# catch_the_light_initial.net
KiCad netlist of a schematic drawn in EAGLE
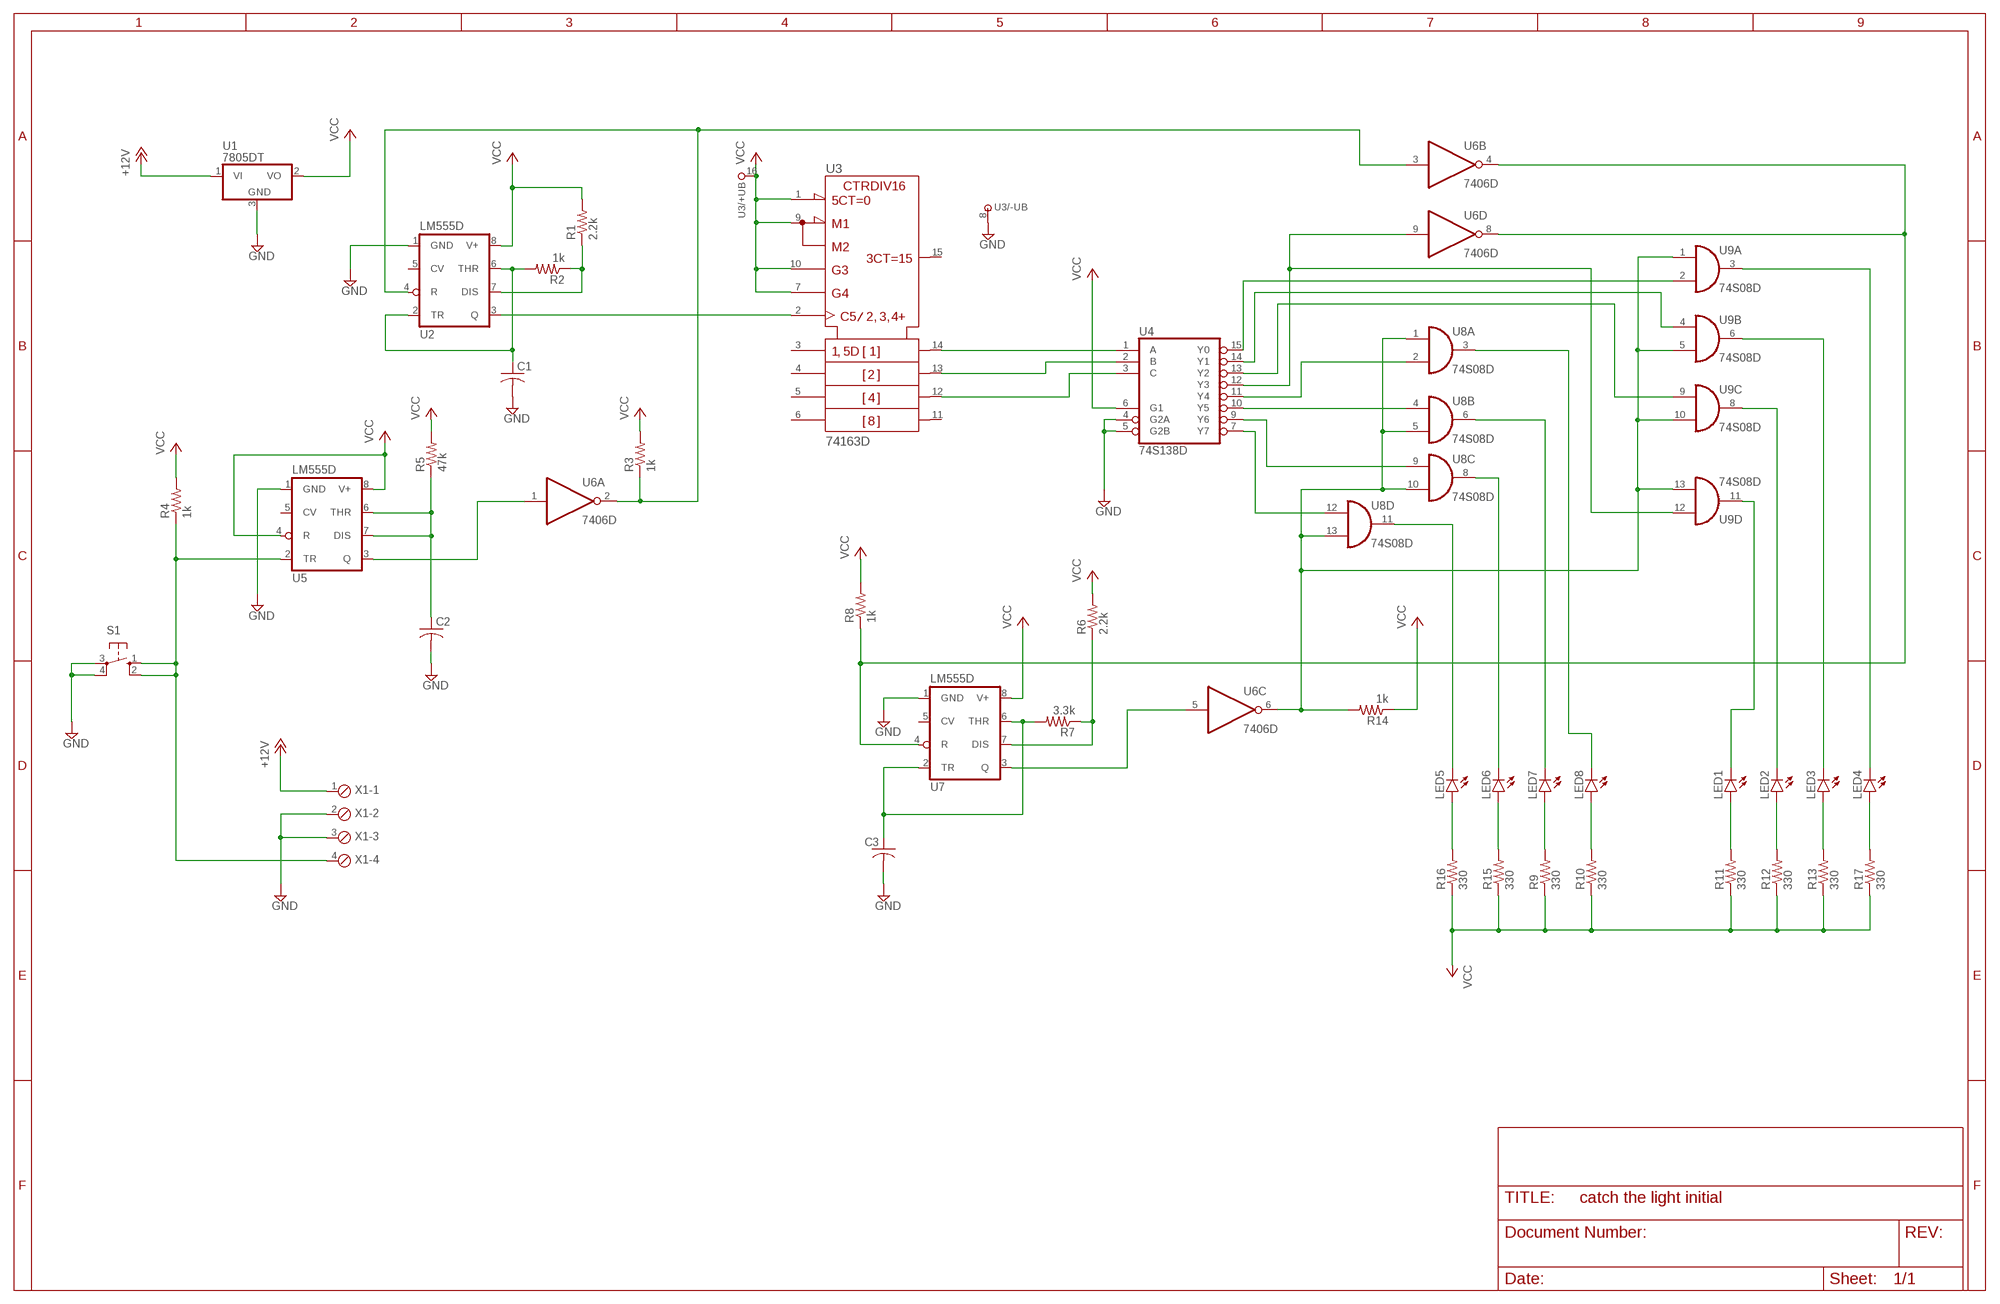
[diagram p0: schematic, sheet 1]

(export (version "E")
  (design (tool "Eeschema 10.0.6"))
  (components
    (comp (ref "C1")
      (value "C-USC0805")
      (footprint "eagle-import:C0805")
      (libsource (lib "eagle-import") (part "C-USC0805"))
    )
    (comp (ref "C2")
      (value "C-USC0805")
      (footprint "eagle-import:C0805")
      (libsource (lib "eagle-import") (part "C-USC0805"))
    )
    (comp (ref "C3")
      (value "C-USC0805")
      (footprint "eagle-import:C0805")
      (libsource (lib "eagle-import") (part "C-USC0805"))
    )
    (comp (ref "LED1")
      (value "LEDCHIP-LED0805")
      (footprint "eagle-import:CHIP-LED0805")
      (libsource (lib "eagle-import") (part "LEDCHIP-LED0805"))
    )
    (comp (ref "LED2")
      (value "LEDCHIP-LED0805")
      (footprint "eagle-import:CHIP-LED0805")
      (libsource (lib "eagle-import") (part "LEDCHIP-LED0805"))
    )
    (comp (ref "LED3")
      (value "LEDCHIP-LED0805")
      (footprint "eagle-import:CHIP-LED0805")
      (libsource (lib "eagle-import") (part "LEDCHIP-LED0805"))
    )
    (comp (ref "LED4")
      (value "LEDCHIP-LED0805")
      (footprint "eagle-import:CHIP-LED0805")
      (libsource (lib "eagle-import") (part "LEDCHIP-LED0805"))
    )
    (comp (ref "LED5")
      (value "LEDCHIP-LED0805")
      (footprint "eagle-import:CHIP-LED0805")
      (libsource (lib "eagle-import") (part "LEDCHIP-LED0805"))
    )
    (comp (ref "LED6")
      (value "LEDCHIP-LED0805")
      (footprint "eagle-import:CHIP-LED0805")
      (libsource (lib "eagle-import") (part "LEDCHIP-LED0805"))
    )
    (comp (ref "LED7")
      (value "LEDCHIP-LED0805")
      (footprint "eagle-import:CHIP-LED0805")
      (libsource (lib "eagle-import") (part "LEDCHIP-LED0805"))
    )
    (comp (ref "LED8")
      (value "LEDCHIP-LED0805")
      (footprint "eagle-import:CHIP-LED0805")
      (libsource (lib "eagle-import") (part "LEDCHIP-LED0805"))
    )
    (comp (ref "R1")
      (value "2.2k")
      (footprint "eagle-import:R0805")
      (libsource (lib "eagle-import") (part "R-US_R0805"))
    )
    (comp (ref "R2")
      (value "1k")
      (footprint "eagle-import:R0805")
      (libsource (lib "eagle-import") (part "R-US_R0805"))
    )
    (comp (ref "R3")
      (value "1k")
      (footprint "eagle-import:R0805")
      (libsource (lib "eagle-import") (part "R-US_R0805"))
    )
    (comp (ref "R4")
      (value "1k")
      (footprint "eagle-import:R0805")
      (libsource (lib "eagle-import") (part "R-US_R0805"))
    )
    (comp (ref "R5")
      (value "47k")
      (footprint "eagle-import:R0805")
      (libsource (lib "eagle-import") (part "R-US_R0805"))
    )
    (comp (ref "R6")
      (value "2.2k")
      (footprint "eagle-import:R0805")
      (libsource (lib "eagle-import") (part "R-US_R0805"))
    )
    (comp (ref "R7")
      (value "3.3k")
      (footprint "eagle-import:R0805")
      (libsource (lib "eagle-import") (part "R-US_R0805"))
    )
    (comp (ref "R8")
      (value "1k")
      (footprint "eagle-import:R0805")
      (libsource (lib "eagle-import") (part "R-US_R0805"))
    )
    (comp (ref "R9")
      (value "330")
      (footprint "eagle-import:R0805")
      (libsource (lib "eagle-import") (part "R-US_R0805"))
    )
    (comp (ref "R10")
      (value "330")
      (footprint "eagle-import:R0805")
      (libsource (lib "eagle-import") (part "R-US_R0805"))
    )
    (comp (ref "R11")
      (value "330")
      (footprint "eagle-import:R0805")
      (libsource (lib "eagle-import") (part "R-US_R0805"))
    )
    (comp (ref "R12")
      (value "330")
      (footprint "eagle-import:R0805")
      (libsource (lib "eagle-import") (part "R-US_R0805"))
    )
    (comp (ref "R13")
      (value "330")
      (footprint "eagle-import:R0805")
      (libsource (lib "eagle-import") (part "R-US_R0805"))
    )
    (comp (ref "R14")
      (value "1k")
      (footprint "eagle-import:R0805")
      (libsource (lib "eagle-import") (part "R-US_R0805"))
    )
    (comp (ref "R15")
      (value "330")
      (footprint "eagle-import:R0805")
      (libsource (lib "eagle-import") (part "R-US_R0805"))
    )
    (comp (ref "R16")
      (value "330")
      (footprint "eagle-import:R0805")
      (libsource (lib "eagle-import") (part "R-US_R0805"))
    )
    (comp (ref "R17")
      (value "330")
      (footprint "eagle-import:R0805")
      (libsource (lib "eagle-import") (part "R-US_R0805"))
    )
    (comp (ref "S1")
      (value "10-XX")
      (footprint "eagle-import:B3F-10XX")
      (fields (field (name "MPN") "B3F-1000"))
      (libsource (lib "eagle-import") (part "10-XX"))
    )
    (comp (ref "U1")
      (value "7805DT")
      (footprint "eagle-import:TO252")
      (libsource (lib "eagle-import") (part "78DT05"))
    )
    (comp (ref "U2")
      (value "LM555D")
      (footprint "eagle-import:SO08")
      (libsource (lib "eagle-import") (part "555DLM"))
    )
    (comp (ref "U3")
      (value "74163D")
      (footprint "eagle-import:SO16")
      (libsource (lib "eagle-import") (part "74163D"))
    )
    (comp (ref "U4")
      (value "74S138D")
      (footprint "eagle-import:SO16")
      (libsource (lib "eagle-import") (part "74138DS"))
    )
    (comp (ref "U5")
      (value "LM555D")
      (footprint "eagle-import:SO08")
      (libsource (lib "eagle-import") (part "555DLM"))
    )
    (comp (ref "U6")
      (value "7406D")
      (footprint "eagle-import:SO14")
      (libsource (lib "eagle-import") (part "7406D"))
    )
    (comp (ref "U7")
      (value "LM555D")
      (footprint "eagle-import:SO08")
      (libsource (lib "eagle-import") (part "555DLM"))
    )
    (comp (ref "U8")
      (value "74S08D")
      (footprint "eagle-import:SO14")
      (libsource (lib "eagle-import") (part "7408DS"))
    )
    (comp (ref "U9")
      (value "74S08D")
      (footprint "eagle-import:SO14")
      (libsource (lib "eagle-import") (part "7408DS"))
    )
    (comp (ref "X1")
      (value "MPT4")
      (footprint "eagle-import:4POL254")
      (libsource (lib "eagle-import") (part "MPT4"))
    )
  )
  (nets
    (net (code "1") (name "+12V") (class "Default")
      (node (ref "U1") (pin "1") (pinfunction "VI_1") (pintype "input"))
      (node (ref "X1") (pin "1") (pinfunction "1_1") (pintype "passive"))
    )
    (net (code "2") (name "GND") (class "Default")
      (node (ref "C1") (pin "2") (pinfunction "2_2") (pintype "passive"))
      (node (ref "C2") (pin "2") (pinfunction "2_2") (pintype "passive"))
      (node (ref "C3") (pin "2") (pinfunction "2_2") (pintype "passive"))
      (node (ref "S1") (pin "3") (pinfunction "P_3") (pintype "passive"))
      (node (ref "S1") (pin "4") (pinfunction "P1_4") (pintype "passive"))
      (node (ref "U1") (pin "3") (pinfunction "GND_3") (pintype "passive"))
      (node (ref "U2") (pin "1") (pinfunction "GND_1") (pintype "power_in"))
      (node (ref "U3") (pin "8") (pinfunction "-UB_8") (pintype "power_in"))
      (node (ref "U4") (pin "4") (pinfunction "G2A_4") (pintype "input"))
      (node (ref "U4") (pin "5") (pinfunction "G2B_5") (pintype "input"))
      (node (ref "U5") (pin "1") (pinfunction "GND_1") (pintype "power_in"))
      (node (ref "U7") (pin "1") (pinfunction "GND_1") (pintype "power_in"))
      (node (ref "X1") (pin "2") (pinfunction "1_2") (pintype "passive"))
      (node (ref "X1") (pin "3") (pinfunction "1_3") (pintype "passive"))
    )
    (net (code "3") (name "Net-(LED1-PadA)") (class "Default")
      (node (ref "LED1") (pin "A") (pinfunction "A_A") (pintype "passive"))
      (node (ref "R11") (pin "2") (pinfunction "2_2") (pintype "passive"))
    )
    (net (code "4") (name "Net-(LED2-PadA)") (class "Default")
      (node (ref "LED2") (pin "A") (pinfunction "A_A") (pintype "passive"))
      (node (ref "R12") (pin "2") (pinfunction "2_2") (pintype "passive"))
    )
    (net (code "5") (name "Net-(LED3-PadA)") (class "Default")
      (node (ref "LED3") (pin "A") (pinfunction "A_A") (pintype "passive"))
      (node (ref "R13") (pin "2") (pinfunction "2_2") (pintype "passive"))
    )
    (net (code "6") (name "Net-(LED4-PadA)") (class "Default")
      (node (ref "LED4") (pin "A") (pinfunction "A_A") (pintype "passive"))
      (node (ref "R17") (pin "2") (pinfunction "2_2") (pintype "passive"))
    )
    (net (code "7") (name "Net-(LED5-PadA)") (class "Default")
      (node (ref "LED5") (pin "A") (pinfunction "A_A") (pintype "passive"))
      (node (ref "R16") (pin "2") (pinfunction "2_2") (pintype "passive"))
    )
    (net (code "8") (name "Net-(LED6-PadA)") (class "Default")
      (node (ref "LED6") (pin "A") (pinfunction "A_A") (pintype "passive"))
      (node (ref "R15") (pin "2") (pinfunction "2_2") (pintype "passive"))
    )
    (net (code "9") (name "Net-(LED7-PadA)") (class "Default")
      (node (ref "LED7") (pin "A") (pinfunction "A_A") (pintype "passive"))
      (node (ref "R9") (pin "2") (pinfunction "2_2") (pintype "passive"))
    )
    (net (code "10") (name "Net-(LED8-PadA)") (class "Default")
      (node (ref "LED8") (pin "A") (pinfunction "A_A") (pintype "passive"))
      (node (ref "R10") (pin "2") (pinfunction "2_2") (pintype "passive"))
    )
    (net (code "11") (name "Net-(S1-S)") (class "Default")
      (node (ref "R4") (pin "1") (pinfunction "1_1") (pintype "passive"))
      (node (ref "S1") (pin "1") (pinfunction "S_1") (pintype "passive"))
      (node (ref "S1") (pin "2") (pinfunction "S1_2") (pintype "passive"))
      (node (ref "U5") (pin "2") (pinfunction "TR_2") (pintype "input"))
      (node (ref "X1") (pin "4") (pinfunction "1_4") (pintype "passive"))
    )
    (net (code "12") (name "Net-(U2-DIS)") (class "Default")
      (node (ref "R1") (pin "1") (pinfunction "1_1") (pintype "passive"))
      (node (ref "R2") (pin "1") (pinfunction "1_1") (pintype "passive"))
      (node (ref "U2") (pin "7") (pinfunction "DIS_7") (pintype "input"))
    )
    (net (code "13") (name "Net-(U2-Q)") (class "Default")
      (node (ref "U2") (pin "3") (pinfunction "Q_3") (pintype "output"))
      (node (ref "U3") (pin "2") (pinfunction "CLK_2") (pintype "input"))
    )
    (net (code "14") (name "Net-(U2-R)") (class "Default")
      (node (ref "R3") (pin "1") (pinfunction "1_1") (pintype "passive"))
      (node (ref "U2") (pin "4") (pinfunction "R_4") (pintype "input"))
      (node (ref "U6") (pin "2") (pinfunction "O_2") (pintype "open_collector"))
      (node (ref "U6") (pin "3") (pinfunction "I_3") (pintype "input"))
    )
    (net (code "15") (name "Net-(U2-THR)") (class "Default")
      (node (ref "C1") (pin "1") (pinfunction "1_1") (pintype "passive"))
      (node (ref "R2") (pin "2") (pinfunction "2_2") (pintype "passive"))
      (node (ref "U2") (pin "2") (pinfunction "TR_2") (pintype "input"))
      (node (ref "U2") (pin "6") (pinfunction "THR_6") (pintype "input"))
    )
    (net (code "16") (name "Net-(U3C-QA)") (class "Default")
      (node (ref "U3") (pin "14") (pinfunction "QA_14") (pintype "output"))
      (node (ref "U4") (pin "1") (pinfunction "A_1") (pintype "input"))
    )
    (net (code "17") (name "Net-(U3C-QB)") (class "Default")
      (node (ref "U3") (pin "13") (pinfunction "QB_13") (pintype "output"))
      (node (ref "U4") (pin "2") (pinfunction "B_2") (pintype "input"))
    )
    (net (code "18") (name "Net-(U3C-QC)") (class "Default")
      (node (ref "U3") (pin "12") (pinfunction "QC_12") (pintype "output"))
      (node (ref "U4") (pin "3") (pinfunction "C_3") (pintype "input"))
    )
    (net (code "19") (name "Net-(U4A-Y0)") (class "Default")
      (node (ref "U4") (pin "15") (pinfunction "Y0_15") (pintype "output"))
      (node (ref "U9") (pin "2") (pinfunction "I1_2") (pintype "input"))
    )
    (net (code "20") (name "Net-(U4A-Y1)") (class "Default")
      (node (ref "U4") (pin "14") (pinfunction "Y1_14") (pintype "output"))
      (node (ref "U9") (pin "4") (pinfunction "I0_4") (pintype "input"))
    )
    (net (code "21") (name "Net-(U4A-Y2)") (class "Default")
      (node (ref "U4") (pin "13") (pinfunction "Y2_13") (pintype "output"))
      (node (ref "U9") (pin "9") (pinfunction "I0_9") (pintype "input"))
    )
    (net (code "22") (name "Net-(U4A-Y3)") (class "Default")
      (node (ref "U4") (pin "12") (pinfunction "Y3_12") (pintype "output"))
      (node (ref "U6") (pin "9") (pinfunction "I_9") (pintype "input"))
      (node (ref "U9") (pin "12") (pinfunction "I0_12") (pintype "input"))
    )
    (net (code "23") (name "Net-(U4A-Y4)") (class "Default")
      (node (ref "U4") (pin "11") (pinfunction "Y4_11") (pintype "output"))
      (node (ref "U8") (pin "2") (pinfunction "I1_2") (pintype "input"))
    )
    (net (code "24") (name "Net-(U4A-Y5)") (class "Default")
      (node (ref "U4") (pin "10") (pinfunction "Y5_10") (pintype "output"))
      (node (ref "U8") (pin "4") (pinfunction "I0_4") (pintype "input"))
    )
    (net (code "25") (name "Net-(U4A-Y6)") (class "Default")
      (node (ref "U4") (pin "9") (pinfunction "Y6_9") (pintype "output"))
      (node (ref "U8") (pin "9") (pinfunction "I0_9") (pintype "input"))
    )
    (net (code "26") (name "Net-(U4A-Y7)") (class "Default")
      (node (ref "U4") (pin "7") (pinfunction "Y7_7") (pintype "output"))
      (node (ref "U8") (pin "12") (pinfunction "I0_12") (pintype "input"))
    )
    (net (code "27") (name "Net-(U5-DIS)") (class "Default")
      (node (ref "C2") (pin "1") (pinfunction "1_1") (pintype "passive"))
      (node (ref "R5") (pin "1") (pinfunction "1_1") (pintype "passive"))
      (node (ref "U5") (pin "6") (pinfunction "THR_6") (pintype "input"))
      (node (ref "U5") (pin "7") (pinfunction "DIS_7") (pintype "input"))
    )
    (net (code "28") (name "Net-(U5-Q)") (class "Default")
      (node (ref "U5") (pin "3") (pinfunction "Q_3") (pintype "output"))
      (node (ref "U6") (pin "1") (pinfunction "I_1") (pintype "input"))
    )
    (net (code "29") (name "Net-(U6B-O)") (class "Default")
      (node (ref "R8") (pin "1") (pinfunction "1_1") (pintype "passive"))
      (node (ref "U6") (pin "4") (pinfunction "O_4") (pintype "open_collector"))
      (node (ref "U6") (pin "8") (pinfunction "O_8") (pintype "open_collector"))
      (node (ref "U7") (pin "4") (pinfunction "R_4") (pintype "input"))
    )
    (net (code "30") (name "Net-(U6C-I)") (class "Default")
      (node (ref "U6") (pin "5") (pinfunction "I_5") (pintype "input"))
      (node (ref "U7") (pin "3") (pinfunction "Q_3") (pintype "output"))
    )
    (net (code "31") (name "Net-(U6C-O)") (class "Default")
      (node (ref "R14") (pin "2") (pinfunction "2_2") (pintype "passive"))
      (node (ref "U6") (pin "6") (pinfunction "O_6") (pintype "open_collector"))
      (node (ref "U8") (pin "1") (pinfunction "I0_1") (pintype "input"))
      (node (ref "U8") (pin "10") (pinfunction "I1_10") (pintype "input"))
      (node (ref "U8") (pin "13") (pinfunction "I1_13") (pintype "input"))
      (node (ref "U8") (pin "5") (pinfunction "I1_5") (pintype "input"))
      (node (ref "U9") (pin "1") (pinfunction "I0_1") (pintype "input"))
      (node (ref "U9") (pin "10") (pinfunction "I1_10") (pintype "input"))
      (node (ref "U9") (pin "13") (pinfunction "I1_13") (pintype "input"))
      (node (ref "U9") (pin "5") (pinfunction "I1_5") (pintype "input"))
    )
    (net (code "32") (name "Net-(U7-DIS)") (class "Default")
      (node (ref "R6") (pin "1") (pinfunction "1_1") (pintype "passive"))
      (node (ref "R7") (pin "1") (pinfunction "1_1") (pintype "passive"))
      (node (ref "U7") (pin "7") (pinfunction "DIS_7") (pintype "input"))
    )
    (net (code "33") (name "Net-(U7-THR)") (class "Default")
      (node (ref "C3") (pin "1") (pinfunction "1_1") (pintype "passive"))
      (node (ref "R7") (pin "2") (pinfunction "2_2") (pintype "passive"))
      (node (ref "U7") (pin "2") (pinfunction "TR_2") (pintype "input"))
      (node (ref "U7") (pin "6") (pinfunction "THR_6") (pintype "input"))
    )
    (net (code "34") (name "Net-(U8A-O)") (class "Default")
      (node (ref "LED8") (pin "C") (pinfunction "C_C") (pintype "passive"))
      (node (ref "U8") (pin "3") (pinfunction "O_3") (pintype "output"))
    )
    (net (code "35") (name "Net-(U8B-O)") (class "Default")
      (node (ref "LED7") (pin "C") (pinfunction "C_C") (pintype "passive"))
      (node (ref "U8") (pin "6") (pinfunction "O_6") (pintype "output"))
    )
    (net (code "36") (name "Net-(U8C-O)") (class "Default")
      (node (ref "LED6") (pin "C") (pinfunction "C_C") (pintype "passive"))
      (node (ref "U8") (pin "8") (pinfunction "O_8") (pintype "output"))
    )
    (net (code "37") (name "Net-(U8D-O)") (class "Default")
      (node (ref "LED5") (pin "C") (pinfunction "C_C") (pintype "passive"))
      (node (ref "U8") (pin "11") (pinfunction "O_11") (pintype "output"))
    )
    (net (code "38") (name "Net-(U9A-O)") (class "Default")
      (node (ref "LED4") (pin "C") (pinfunction "C_C") (pintype "passive"))
      (node (ref "U9") (pin "3") (pinfunction "O_3") (pintype "output"))
    )
    (net (code "39") (name "Net-(U9B-O)") (class "Default")
      (node (ref "LED3") (pin "C") (pinfunction "C_C") (pintype "passive"))
      (node (ref "U9") (pin "6") (pinfunction "O_6") (pintype "output"))
    )
    (net (code "40") (name "Net-(U9C-O)") (class "Default")
      (node (ref "LED2") (pin "C") (pinfunction "C_C") (pintype "passive"))
      (node (ref "U9") (pin "8") (pinfunction "O_8") (pintype "output"))
    )
    (net (code "41") (name "Net-(U9D-O)") (class "Default")
      (node (ref "LED1") (pin "C") (pinfunction "C_C") (pintype "passive"))
      (node (ref "U9") (pin "11") (pinfunction "O_11") (pintype "output"))
    )
    (net (code "42") (name "VCC") (class "Default")
      (node (ref "R1") (pin "2") (pinfunction "2_2") (pintype "passive"))
      (node (ref "R10") (pin "1") (pinfunction "1_1") (pintype "passive"))
      (node (ref "R11") (pin "1") (pinfunction "1_1") (pintype "passive"))
      (node (ref "R12") (pin "1") (pinfunction "1_1") (pintype "passive"))
      (node (ref "R13") (pin "1") (pinfunction "1_1") (pintype "passive"))
      (node (ref "R14") (pin "1") (pinfunction "1_1") (pintype "passive"))
      (node (ref "R15") (pin "1") (pinfunction "1_1") (pintype "passive"))
      (node (ref "R16") (pin "1") (pinfunction "1_1") (pintype "passive"))
      (node (ref "R17") (pin "1") (pinfunction "1_1") (pintype "passive"))
      (node (ref "R3") (pin "2") (pinfunction "2_2") (pintype "passive"))
      (node (ref "R4") (pin "2") (pinfunction "2_2") (pintype "passive"))
      (node (ref "R5") (pin "2") (pinfunction "2_2") (pintype "passive"))
      (node (ref "R6") (pin "2") (pinfunction "2_2") (pintype "passive"))
      (node (ref "R8") (pin "2") (pinfunction "2_2") (pintype "passive"))
      (node (ref "R9") (pin "1") (pinfunction "1_1") (pintype "passive"))
      (node (ref "U1") (pin "2") (pinfunction "VO_2") (pintype "passive"))
      (node (ref "U2") (pin "8") (pinfunction "V+_8") (pintype "power_in"))
      (node (ref "U3") (pin "1") (pinfunction "~{CLR}_1") (pintype "input"))
      (node (ref "U3") (pin "10") (pinfunction "ENT_10") (pintype "input"))
      (node (ref "U3") (pin "16") (pinfunction "+UB_16") (pintype "power_in"))
      (node (ref "U3") (pin "7") (pinfunction "ENP_7") (pintype "input"))
      (node (ref "U3") (pin "9") (pinfunction "~{LOAD}_9") (pintype "input"))
      (node (ref "U4") (pin "6") (pinfunction "G1_6") (pintype "input"))
      (node (ref "U5") (pin "4") (pinfunction "R_4") (pintype "input"))
      (node (ref "U5") (pin "8") (pinfunction "V+_8") (pintype "power_in"))
      (node (ref "U7") (pin "8") (pinfunction "V+_8") (pintype "power_in"))
    )
    (net (code "43") (name "unconnected-(U2-CV-Pad5)") (class "Default")
      (node (ref "U2") (pin "5") (pinfunction "CV_5") (pintype "input"))
    )
    (net (code "44") (name "unconnected-(U3C-A-Pad3)") (class "Default")
      (node (ref "U3") (pin "3") (pinfunction "A_3") (pintype "input"))
    )
    (net (code "45") (name "unconnected-(U3C-B-Pad4)") (class "Default")
      (node (ref "U3") (pin "4") (pinfunction "B_4") (pintype "input"))
    )
    (net (code "46") (name "unconnected-(U3C-C-Pad5)") (class "Default")
      (node (ref "U3") (pin "5") (pinfunction "C_5") (pintype "input"))
    )
    (net (code "47") (name "unconnected-(U3C-D-Pad6)") (class "Default")
      (node (ref "U3") (pin "6") (pinfunction "D_6") (pintype "input"))
    )
    (net (code "48") (name "unconnected-(U3C-QD-Pad11)") (class "Default")
      (node (ref "U3") (pin "11") (pinfunction "QD_11") (pintype "output"))
    )
    (net (code "49") (name "unconnected-(U3C-RCO-Pad15)") (class "Default")
      (node (ref "U3") (pin "15") (pinfunction "RCO_15") (pintype "output"))
    )
    (net (code "50") (name "unconnected-(U5-CV-Pad5)") (class "Default")
      (node (ref "U5") (pin "5") (pinfunction "CV_5") (pintype "input"))
    )
    (net (code "51") (name "unconnected-(U7-CV-Pad5)") (class "Default")
      (node (ref "U7") (pin "5") (pinfunction "CV_5") (pintype "input"))
    )
  )
)
